# Mechanical.net
KiCad netlist of a schematic drawn in Altium Designer
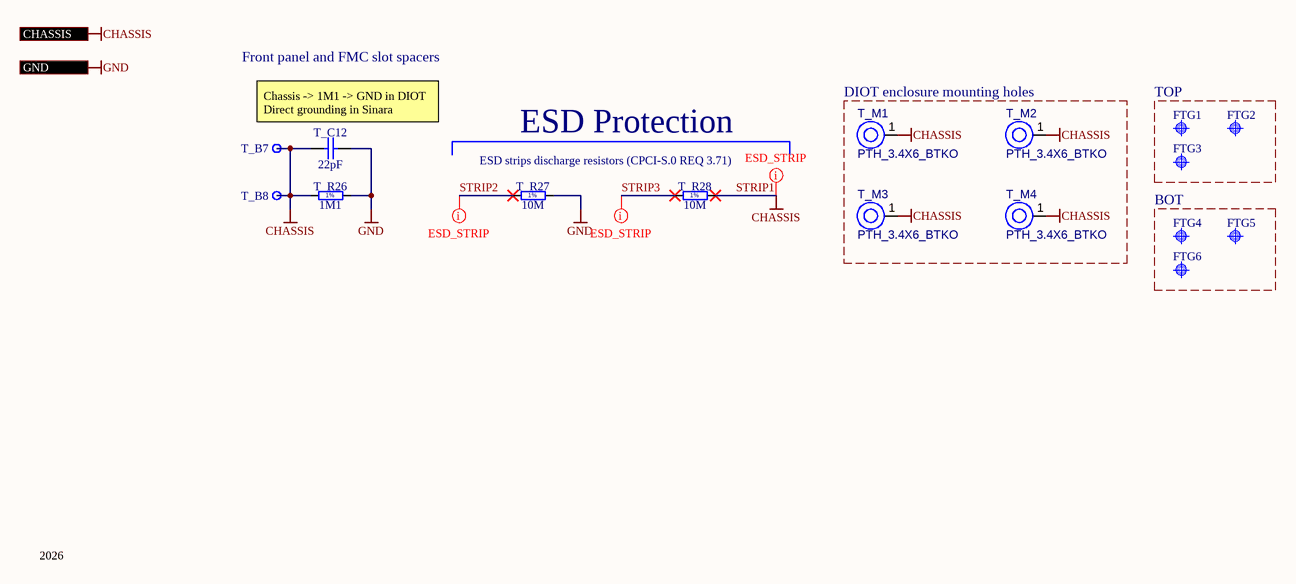
[diagram p0: Mechanical.SchDoc]

(export (version "E")
  (design (tool "Eeschema 10.0.6"))
  (components
    (comp (ref "FTG1")
      (value "Use only in PCB")
      (footprint "FIDUCIAL_TOP_C100-200")
      (description "Fiducial Target")
      (fields (field (name "PART NUMBER") "FIDUCIAL_TARGET_C100-200") (field (name "AUTHOR") "CERN DEM JLC"))
      (libsource (lib "Eletro-mechanical") (part "Fiducial Target"))
    )
    (comp (ref "FTG2")
      (value "Use only in PCB")
      (footprint "FIDUCIAL_TOP_S100-200")
      (description "Fiducial Target")
      (fields (field (name "PART NUMBER") "FIDUCIAL_TARGET_S100-200") (field (name "AUTHOR") "CERN DEM JLC"))
      (libsource (lib "Eletro-mechanical") (part "Fiducial Target"))
    )
    (comp (ref "FTG3")
      (value "Use only in PCB")
      (footprint "FIDUCIAL_TOP_S100-200")
      (description "Fiducial Target")
      (fields (field (name "PART NUMBER") "FIDUCIAL_TARGET_S100-200") (field (name "AUTHOR") "CERN DEM JLC"))
      (libsource (lib "Eletro-mechanical") (part "Fiducial Target"))
    )
    (comp (ref "FTG4")
      (value "Use only in PCB")
      (footprint "FIDUCIAL_TOP_C100-200")
      (description "Fiducial Target")
      (fields (field (name "PART NUMBER") "FIDUCIAL_TARGET_C100-200") (field (name "AUTHOR") "CERN DEM JLC"))
      (libsource (lib "Eletro-mechanical") (part "Fiducial Target"))
    )
    (comp (ref "FTG5")
      (value "Use only in PCB")
      (footprint "FIDUCIAL_TOP_S100-200")
      (description "Fiducial Target")
      (fields (field (name "PART NUMBER") "FIDUCIAL_TARGET_S100-200") (field (name "AUTHOR") "CERN DEM JLC"))
      (libsource (lib "Eletro-mechanical") (part "Fiducial Target"))
    )
    (comp (ref "FTG6")
      (value "Use only in PCB")
      (footprint "FIDUCIAL_TOP_S100-200")
      (description "Fiducial Target")
      (fields (field (name "PART NUMBER") "FIDUCIAL_TARGET_S100-200") (field (name "AUTHOR") "CERN DEM JLC"))
      (libsource (lib "Eletro-mechanical") (part "Fiducial Target"))
    )
    (comp (ref "T_B7")
      (value "Plated Hole")
      (footprint "c600h270")
      (description "Single Terminal Socket")
      (fields (field (name "PART NUMBER") "PLATED_HOLE2.7_PAD6.0") (field (name "AUTHOR") "CERN DEM HF"))
      (libsource (lib "Eletro-mechanical") (part "Single Terminal Socket"))
    )
    (comp (ref "T_B8")
      (value "Plated Hole")
      (footprint "c600h270")
      (description "Single Terminal Socket")
      (fields (field (name "PART NUMBER") "PLATED_HOLE2.7_PAD6.0") (field (name "AUTHOR") "CERN DEM HF"))
      (libsource (lib "Eletro-mechanical") (part "Single Terminal Socket"))
    )
    (comp (ref "T_C12")
      (value "22pF")
      (footprint "CAPC1005X55N")
      (description "Non-polarised capacitor")
      (fields
        (field (name "PART NUMBER") "CC0402_22PF_50V_5%_C0G")
        (field (name "VOLTAGE") "50V")
        (field (name "AUTHOR") "CERN DEM JLC")
      )
      (libsource (lib "Capacitors") (part "Capacitor - non polarized"))
    )
    (comp (ref "T_M1")
      (value "PTH_3.4X6_BTKO")
      (footprint "PTH-M3.4x6.0_BTKO")
      (description "PTH  Hole 3.4, 6mm pad")
      (libsource (lib "TechnoSystem Workspace") (part "PTH3.4x6.0_BTKO"))
    )
    (comp (ref "T_M2")
      (value "PTH_3.4X6_BTKO")
      (footprint "PTH-M3.4x6.0_BTKO")
      (description "PTH  Hole 3.4, 6mm pad")
      (libsource (lib "TechnoSystem Workspace") (part "PTH3.4x6.0_BTKO"))
    )
    (comp (ref "T_M3")
      (value "PTH_3.4X6_BTKO")
      (footprint "PTH-M3.4x6.0_BTKO")
      (description "PTH  Hole 3.4, 6mm pad")
      (libsource (lib "TechnoSystem Workspace") (part "PTH3.4x6.0_BTKO"))
    )
    (comp (ref "T_M4")
      (value "PTH_3.4X6_BTKO")
      (footprint "PTH-M3.4x6.0_BTKO")
      (description "PTH  Hole 3.4, 6mm pad")
      (libsource (lib "TechnoSystem Workspace") (part "PTH3.4x6.0_BTKO"))
    )
    (comp (ref "T_R26")
      (value "1M1")
      (footprint "RESC2012X60N")
      (description "Resistor - 1%")
      (fields
        (field (name "PART NUMBER") "R0805_1M1_1%_0.125W_100PPM")
        (field (name "MANUFACTURER") "GENERIC")
        (field (name "AUTHOR") "CERN DEM JLC")
      )
      (libsource (lib "Resistors") (part "Resistor - 1%"))
    )
    (comp (ref "T_R27")
      (value "10M")
      (footprint "RESC2113X55N")
      (description "Resistor - 1%")
      (fields
        (field (name "PART NUMBER") "R0805_10M_1%_0.125W_100PPM_VISHAY_CRCW e3")
        (field (name "POWER") "0.125W")
        (field (name "AUTHOR") "CERN DEM BC")
      )
      (libsource (lib "Resistors") (part "Resistor - 1%"))
    )
    (comp (ref "T_R28")
      (value "10M")
      (footprint "RESC2113X55N")
      (description "Resistor - 1%")
      (fields
        (field (name "PART NUMBER") "R0805_10M_1%_0.125W_100PPM_VISHAY_CRCW e3")
        (field (name "POWER") "0.125W")
        (field (name "AUTHOR") "CERN DEM BC")
      )
      (libsource (lib "Resistors") (part "Resistor - 1%"))
    )
  )
  (nets
    (net (code "1") (name "/STRIP2") (class "Default")
      (node (ref "T_R27") (pin "1") (pinfunction "1_1") (pintype "passive+no_connect"))
    )
    (net (code "2") (name "/STRIP3") (class "Default")
      (node (ref "T_R28") (pin "1") (pinfunction "1_1") (pintype "passive+no_connect"))
    )
    (net (code "3") (name "CHASSIS") (class "Default")
      (node (ref "T_B7") (pin "1") (pinfunction "1_1") (pintype "bidirectional"))
      (node (ref "T_B8") (pin "1") (pinfunction "1_1") (pintype "bidirectional"))
      (node (ref "T_C12") (pin "1") (pinfunction "1_1") (pintype "passive"))
      (node (ref "T_M1") (pin "1") (pinfunction "H1_1") (pintype "passive"))
      (node (ref "T_M2") (pin "1") (pinfunction "H1_1") (pintype "passive"))
      (node (ref "T_M3") (pin "1") (pinfunction "H1_1") (pintype "passive"))
      (node (ref "T_M4") (pin "1") (pinfunction "H1_1") (pintype "passive"))
      (node (ref "T_R26") (pin "1") (pinfunction "1_1") (pintype "passive"))
      (node (ref "T_R28") (pin "2") (pinfunction "2_2") (pintype "passive"))
    )
    (net (code "4") (name "GND") (class "Default")
      (node (ref "T_C12") (pin "2") (pinfunction "2_2") (pintype "passive"))
      (node (ref "T_R26") (pin "2") (pinfunction "2_2") (pintype "passive"))
      (node (ref "T_R27") (pin "2") (pinfunction "2_2") (pintype "passive"))
    )
  )
)
